# 2.net
KiCad netlist of a schematic drawn in Altium Designer
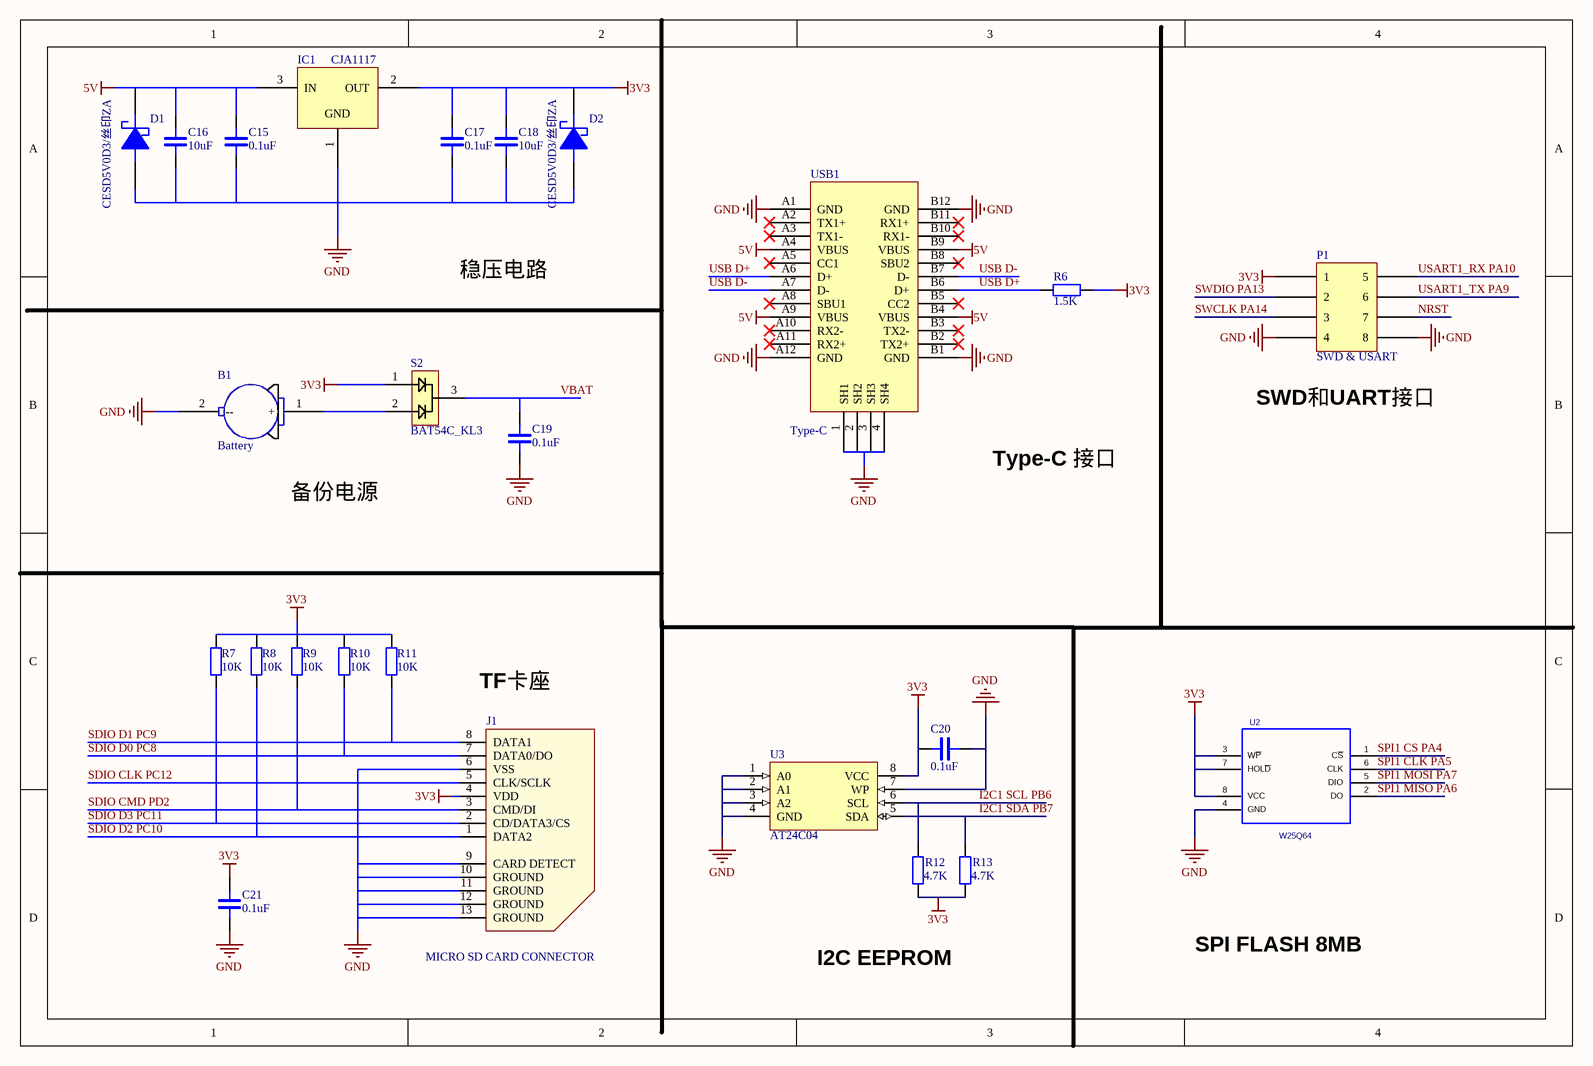
[diagram p0: 主控系统板2.SchDoc]

(export (version "E")
  (design (tool "Eeschema 10.0.6"))
  (components
    (comp (ref "B1")
      (value "Battery")
      (footprint "CR1220")
      (libsource (lib "altium-import") (part "root_2_Battery_"))
    )
    (comp (ref "C15")
      (value "0.1uF")
      (footprint "0603")
      (description "Capacitor")
      (libsource (lib "General") (part "CAP"))
    )
    (comp (ref "C16")
      (value "10uF")
      (footprint "0603")
      (description "Capacitor")
      (libsource (lib "General") (part "CAP"))
    )
    (comp (ref "C17")
      (value "0.1uF")
      (footprint "0603")
      (description "Capacitor")
      (libsource (lib "General") (part "CAP"))
    )
    (comp (ref "C18")
      (value "10uF")
      (footprint "0603")
      (description "Capacitor")
      (libsource (lib "General") (part "CAP"))
    )
    (comp (ref "C19")
      (value "0.1uF")
      (footprint "0603")
      (description "Capacitor")
      (libsource (lib "General") (part "CAP"))
    )
    (comp (ref "C20")
      (value "0.1uF")
      (footprint "0603")
      (description "Capacitor")
      (libsource (lib "General") (part "CAP"))
    )
    (comp (ref "C21")
      (value "0.1uF")
      (footprint "0603")
      (description "Capacitor")
      (libsource (lib "General") (part "CAP"))
    )
    (comp (ref "D1")
      (value "CESD5V0D3/丝印ZA")
      (footprint "SOD323")
      (libsource (lib "altium-import") (part "root_3_TVS_"))
    )
    (comp (ref "D2")
      (value "CESD5V0D3/丝印ZA")
      (footprint "SOD323")
      (libsource (lib "altium-import") (part "root_3_TVS_"))
    )
    (comp (ref "IC1")
      (value "CJA1117")
      (footprint "SOT89")
      (libsource (lib "altium-import") (part "root_0_CJA1117_"))
    )
    (comp (ref "J1")
      (value "MICRO SD CARD CONNECTOR")
      (footprint "MICRO SD CARD CONNECTOR")
      (description "Micro SD Card Connector")
      (libsource (lib "General") (part "MICRO SD CARD CONNECTOR"))
    )
    (comp (ref "P1")
      (value "SWD & USART")
      (footprint "2X4P-2.5MM-SMD")
      (libsource (lib "altium-import") (part "root_0_CON4-X2_"))
    )
    (comp (ref "R6")
      (value "1.5K")
      (footprint "0603")
      (description "Resistor")
      (libsource (lib "") (part "RES_1"))
    )
    (comp (ref "R7")
      (value "10K")
      (footprint "0603")
      (description "Resistor")
      (libsource (lib "General") (part "RES"))
    )
    (comp (ref "R8")
      (value "10K")
      (footprint "0603")
      (description "Resistor")
      (libsource (lib "General") (part "RES"))
    )
    (comp (ref "R9")
      (value "10K")
      (footprint "0603")
      (description "Resistor")
      (libsource (lib "General") (part "RES"))
    )
    (comp (ref "R10")
      (value "10K")
      (footprint "0603")
      (description "Resistor")
      (libsource (lib "General") (part "RES"))
    )
    (comp (ref "R11")
      (value "10K")
      (footprint "0603")
      (description "Resistor")
      (libsource (lib "General") (part "RES"))
    )
    (comp (ref "R12")
      (value "4.7K")
      (footprint "0603")
      (description "Resistor")
      (libsource (lib "General") (part "RES"))
    )
    (comp (ref "R13")
      (value "4.7K")
      (footprint "0603")
      (description "Resistor")
      (libsource (lib "General") (part "RES"))
    )
    (comp (ref "S2")
      (value "BAT54C_KL3")
      (footprint "SOT-23")
      (libsource (lib "altium-import") (part "root_3_BAT54C_KL3_"))
    )
    (comp (ref "U2")
      (value "W25Q64")
      (footprint "SO8WB")
      (libsource (lib "altium-import") (part "root_0_W25Q64_"))
    )
    (comp (ref "U3")
      (value "AT24C04")
      (footprint "SO-8")
      (description "EEPROM")
      (libsource (lib "General") (part "AT24Cxx"))
    )
    (comp (ref "USB1")
      (value "Type-C")
      (footprint "Type-C")
      (libsource (lib "altium-import") (part "root_0_Type-C_"))
    )
  )
  (nets
    (net (code "1") (name "/I2C1 SCL PB6") (class "Default")
      (node (ref "R12") (pin "1") (pinfunction "1_1") (pintype "passive"))
      (node (ref "U3") (pin "6") (pinfunction "SCL_6") (pintype "input"))
    )
    (net (code "2") (name "/I2C1 SDA PB7") (class "Default")
      (node (ref "R13") (pin "1") (pinfunction "1_1") (pintype "passive"))
      (node (ref "U3") (pin "5") (pinfunction "SDA_5") (pintype "bidirectional"))
    )
    (net (code "3") (name "/NRST") (class "Default")
      (node (ref "P1") (pin "7") (pinfunction "7_7") (pintype "passive"))
    )
    (net (code "4") (name "/SDIO CLK PC12") (class "Default")
      (node (ref "J1") (pin "5") (pinfunction "CLK/SCLK_5") (pintype "passive"))
    )
    (net (code "5") (name "/SDIO CMD PD2") (class "Default")
      (node (ref "J1") (pin "3") (pinfunction "CMD/DI_3") (pintype "passive"))
      (node (ref "R9") (pin "2") (pinfunction "2_2") (pintype "passive"))
    )
    (net (code "6") (name "/SDIO D0 PC8") (class "Default")
      (node (ref "J1") (pin "7") (pinfunction "DATA0/DO_7") (pintype "passive"))
      (node (ref "R10") (pin "2") (pinfunction "2_2") (pintype "passive"))
    )
    (net (code "7") (name "/SDIO D1 PC9") (class "Default")
      (node (ref "J1") (pin "8") (pinfunction "DATA1_8") (pintype "passive"))
      (node (ref "R11") (pin "2") (pinfunction "2_2") (pintype "passive"))
    )
    (net (code "8") (name "/SDIO D2 PC10") (class "Default")
      (node (ref "J1") (pin "1") (pinfunction "DATA2_1") (pintype "passive"))
      (node (ref "R8") (pin "2") (pinfunction "2_2") (pintype "passive"))
    )
    (net (code "9") (name "/SDIO D3 PC11") (class "Default")
      (node (ref "J1") (pin "2") (pinfunction "CD/DATA3/CS_2") (pintype "passive"))
      (node (ref "R7") (pin "2") (pinfunction "2_2") (pintype "passive"))
    )
    (net (code "10") (name "/SPI1 CLK PA5") (class "Default")
      (node (ref "U2") (pin "6") (pinfunction "CLK_6") (pintype "passive"))
    )
    (net (code "11") (name "/SPI1 CS PA4") (class "Default")
      (node (ref "U2") (pin "1") (pinfunction "C~{S}_1") (pintype "passive"))
    )
    (net (code "12") (name "/SPI1 MISO PA6") (class "Default")
      (node (ref "U2") (pin "2") (pinfunction "DO_2") (pintype "passive"))
    )
    (net (code "13") (name "/SPI1 MOSI PA7") (class "Default")
      (node (ref "U2") (pin "5") (pinfunction "DIO_5") (pintype "passive"))
    )
    (net (code "14") (name "/SWCLK PA14") (class "Default")
      (node (ref "P1") (pin "3") (pinfunction "3_3") (pintype "passive"))
    )
    (net (code "15") (name "/SWDIO PA13") (class "Default")
      (node (ref "P1") (pin "2") (pinfunction "2_2") (pintype "passive"))
    )
    (net (code "16") (name "/USART1_RX PA10") (class "Default")
      (node (ref "P1") (pin "5") (pinfunction "5_5") (pintype "passive"))
    )
    (net (code "17") (name "/USART1_TX PA9") (class "Default")
      (node (ref "P1") (pin "6") (pinfunction "6_6") (pintype "passive"))
    )
    (net (code "18") (name "/USB D+") (class "Default")
      (node (ref "R6") (pin "2") (pinfunction "2_2") (pintype "passive"))
      (node (ref "USB1") (pin "A6") (pinfunction "D+_A6") (pintype "passive"))
      (node (ref "USB1") (pin "B6") (pinfunction "D+_B6") (pintype "passive"))
    )
    (net (code "19") (name "/USB D-") (class "Default")
      (node (ref "USB1") (pin "A7") (pinfunction "D-_A7") (pintype "passive"))
      (node (ref "USB1") (pin "B7") (pinfunction "D-_B7") (pintype "passive"))
    )
    (net (code "20") (name "/VBAT") (class "Default")
      (node (ref "C19") (pin "1") (pinfunction "1_1") (pintype "passive"))
      (node (ref "S2") (pin "3") (pinfunction "3_3") (pintype "passive"))
    )
    (net (code "21") (name "3V3") (class "Default")
      (node (ref "C17") (pin "1") (pinfunction "1_1") (pintype "passive"))
      (node (ref "C18") (pin "1") (pinfunction "1_1") (pintype "passive"))
      (node (ref "C20") (pin "1") (pinfunction "1_1") (pintype "passive"))
      (node (ref "C21") (pin "1") (pinfunction "1_1") (pintype "passive"))
      (node (ref "D2") (pin "2") (pinfunction "-_2") (pintype "passive"))
      (node (ref "IC1") (pin "2") (pinfunction "OUT_2") (pintype "passive"))
      (node (ref "J1") (pin "4") (pinfunction "VDD_4") (pintype "power_in"))
      (node (ref "P1") (pin "1") (pinfunction "1_1") (pintype "passive"))
      (node (ref "R10") (pin "1") (pinfunction "1_1") (pintype "passive"))
      (node (ref "R11") (pin "1") (pinfunction "1_1") (pintype "passive"))
      (node (ref "R12") (pin "2") (pinfunction "2_2") (pintype "passive"))
      (node (ref "R13") (pin "2") (pinfunction "2_2") (pintype "passive"))
      (node (ref "R6") (pin "1") (pinfunction "1_1") (pintype "passive"))
      (node (ref "R7") (pin "1") (pinfunction "1_1") (pintype "passive"))
      (node (ref "R8") (pin "1") (pinfunction "1_1") (pintype "passive"))
      (node (ref "R9") (pin "1") (pinfunction "1_1") (pintype "passive"))
      (node (ref "S2") (pin "1") (pintype "passive"))
      (node (ref "U2") (pin "3") (pinfunction "W~{P}_3") (pintype "passive"))
      (node (ref "U2") (pin "7") (pinfunction "HOL~{D}_7") (pintype "passive"))
      (node (ref "U2") (pin "8") (pinfunction "VCC_8") (pintype "passive"))
      (node (ref "U3") (pin "8") (pinfunction "VCC_8") (pintype "power_in"))
    )
    (net (code "22") (name "5V") (class "Default")
      (node (ref "C15") (pin "1") (pinfunction "1_1") (pintype "passive"))
      (node (ref "C16") (pin "1") (pinfunction "1_1") (pintype "passive"))
      (node (ref "D1") (pin "2") (pinfunction "-_2") (pintype "passive"))
      (node (ref "IC1") (pin "3") (pinfunction "IN_3") (pintype "passive"))
      (node (ref "USB1") (pin "A4") (pinfunction "VBUS_A4") (pintype "passive"))
      (node (ref "USB1") (pin "A9") (pinfunction "VBUS_A9") (pintype "passive"))
      (node (ref "USB1") (pin "B4") (pinfunction "VBUS_B4") (pintype "passive"))
      (node (ref "USB1") (pin "B9") (pinfunction "VBUS_B9") (pintype "passive"))
    )
    (net (code "23") (name "GND") (class "Default")
      (node (ref "B1") (pin "2") (pinfunction "--_2") (pintype "passive"))
      (node (ref "C15") (pin "2") (pinfunction "2_2") (pintype "passive"))
      (node (ref "C16") (pin "2") (pinfunction "2_2") (pintype "passive"))
      (node (ref "C17") (pin "2") (pinfunction "2_2") (pintype "passive"))
      (node (ref "C18") (pin "2") (pinfunction "2_2") (pintype "passive"))
      (node (ref "C19") (pin "2") (pinfunction "2_2") (pintype "passive"))
      (node (ref "C20") (pin "2") (pinfunction "2_2") (pintype "passive"))
      (node (ref "C21") (pin "2") (pinfunction "2_2") (pintype "passive"))
      (node (ref "D1") (pin "1") (pinfunction "+_1") (pintype "passive"))
      (node (ref "D2") (pin "1") (pinfunction "+_1") (pintype "passive"))
      (node (ref "IC1") (pin "1") (pinfunction "GND_1") (pintype "passive"))
      (node (ref "J1") (pin "10") (pinfunction "GROUND_10") (pintype "passive"))
      (node (ref "J1") (pin "11") (pinfunction "GROUND_11") (pintype "passive"))
      (node (ref "J1") (pin "12") (pinfunction "GROUND_12") (pintype "passive"))
      (node (ref "J1") (pin "13") (pinfunction "GROUND_13") (pintype "passive"))
      (node (ref "J1") (pin "6") (pinfunction "VSS_6") (pintype "power_in"))
      (node (ref "J1") (pin "9") (pinfunction "CARD_DETECT_9") (pintype "passive"))
      (node (ref "P1") (pin "4") (pinfunction "4_4") (pintype "passive"))
      (node (ref "P1") (pin "8") (pinfunction "8_8") (pintype "passive"))
      (node (ref "U2") (pin "4") (pinfunction "GND_4") (pintype "passive"))
      (node (ref "U3") (pin "1") (pinfunction "A0_1") (pintype "input"))
      (node (ref "U3") (pin "2") (pinfunction "A1_2") (pintype "input"))
      (node (ref "U3") (pin "3") (pinfunction "A2_3") (pintype "input"))
      (node (ref "U3") (pin "4") (pinfunction "GND_4") (pintype "power_in"))
      (node (ref "U3") (pin "7") (pinfunction "WP_7") (pintype "input"))
      (node (ref "USB1") (pin "1") (pinfunction "SH1_1") (pintype "passive"))
      (node (ref "USB1") (pin "2") (pinfunction "SH2_2") (pintype "passive"))
      (node (ref "USB1") (pin "3") (pinfunction "SH3_3") (pintype "passive"))
      (node (ref "USB1") (pin "4") (pinfunction "SH4_4") (pintype "passive"))
      (node (ref "USB1") (pin "A1") (pinfunction "GND_A1") (pintype "passive"))
      (node (ref "USB1") (pin "A12") (pinfunction "GND_A12") (pintype "passive"))
      (node (ref "USB1") (pin "B1") (pinfunction "GND_B1") (pintype "passive"))
      (node (ref "USB1") (pin "B12") (pinfunction "GND_B12") (pintype "passive"))
    )
    (net (code "24") (name "Net-(B1-+)") (class "Default")
      (node (ref "B1") (pin "1") (pinfunction "+_1") (pintype "passive"))
      (node (ref "S2") (pin "2") (pinfunction "2_2") (pintype "passive"))
    )
    (net (code "25") (name "unconnected-(USB1-CC1-PadA5)") (class "Default")
      (node (ref "USB1") (pin "A5") (pinfunction "CC1_A5") (pintype "passive+no_connect"))
    )
    (net (code "26") (name "unconnected-(USB1-CC2-PadB5)") (class "Default")
      (node (ref "USB1") (pin "B5") (pinfunction "CC2_B5") (pintype "passive+no_connect"))
    )
    (net (code "27") (name "unconnected-(USB1-RX1+-PadB11)") (class "Default")
      (node (ref "USB1") (pin "B11") (pinfunction "RX1+_B11") (pintype "passive+no_connect"))
    )
    (net (code "28") (name "unconnected-(USB1-RX1--PadB10)") (class "Default")
      (node (ref "USB1") (pin "B10") (pinfunction "RX1-_B10") (pintype "passive+no_connect"))
    )
    (net (code "29") (name "unconnected-(USB1-RX2+-PadA11)") (class "Default")
      (node (ref "USB1") (pin "A11") (pinfunction "RX2+_A11") (pintype "passive+no_connect"))
    )
    (net (code "30") (name "unconnected-(USB1-RX2--PadA10)") (class "Default")
      (node (ref "USB1") (pin "A10") (pinfunction "RX2-_A10") (pintype "passive+no_connect"))
    )
    (net (code "31") (name "unconnected-(USB1-SBU1-PadA8)") (class "Default")
      (node (ref "USB1") (pin "A8") (pinfunction "SBU1_A8") (pintype "passive+no_connect"))
    )
    (net (code "32") (name "unconnected-(USB1-SBU2-PadB8)") (class "Default")
      (node (ref "USB1") (pin "B8") (pinfunction "SBU2_B8") (pintype "passive+no_connect"))
    )
    (net (code "33") (name "unconnected-(USB1-TX1+-PadA2)") (class "Default")
      (node (ref "USB1") (pin "A2") (pinfunction "TX1+_A2") (pintype "passive+no_connect"))
    )
    (net (code "34") (name "unconnected-(USB1-TX1--PadA3)") (class "Default")
      (node (ref "USB1") (pin "A3") (pinfunction "TX1-_A3") (pintype "passive+no_connect"))
    )
    (net (code "35") (name "unconnected-(USB1-TX2+-PadB2)") (class "Default")
      (node (ref "USB1") (pin "B2") (pinfunction "TX2+_B2") (pintype "passive+no_connect"))
    )
    (net (code "36") (name "unconnected-(USB1-TX2--PadB3)") (class "Default")
      (node (ref "USB1") (pin "B3") (pinfunction "TX2-_B3") (pintype "passive+no_connect"))
    )
  )
)
